# Board-Back.net
KiCad netlist of a schematic drawn in EAGLE
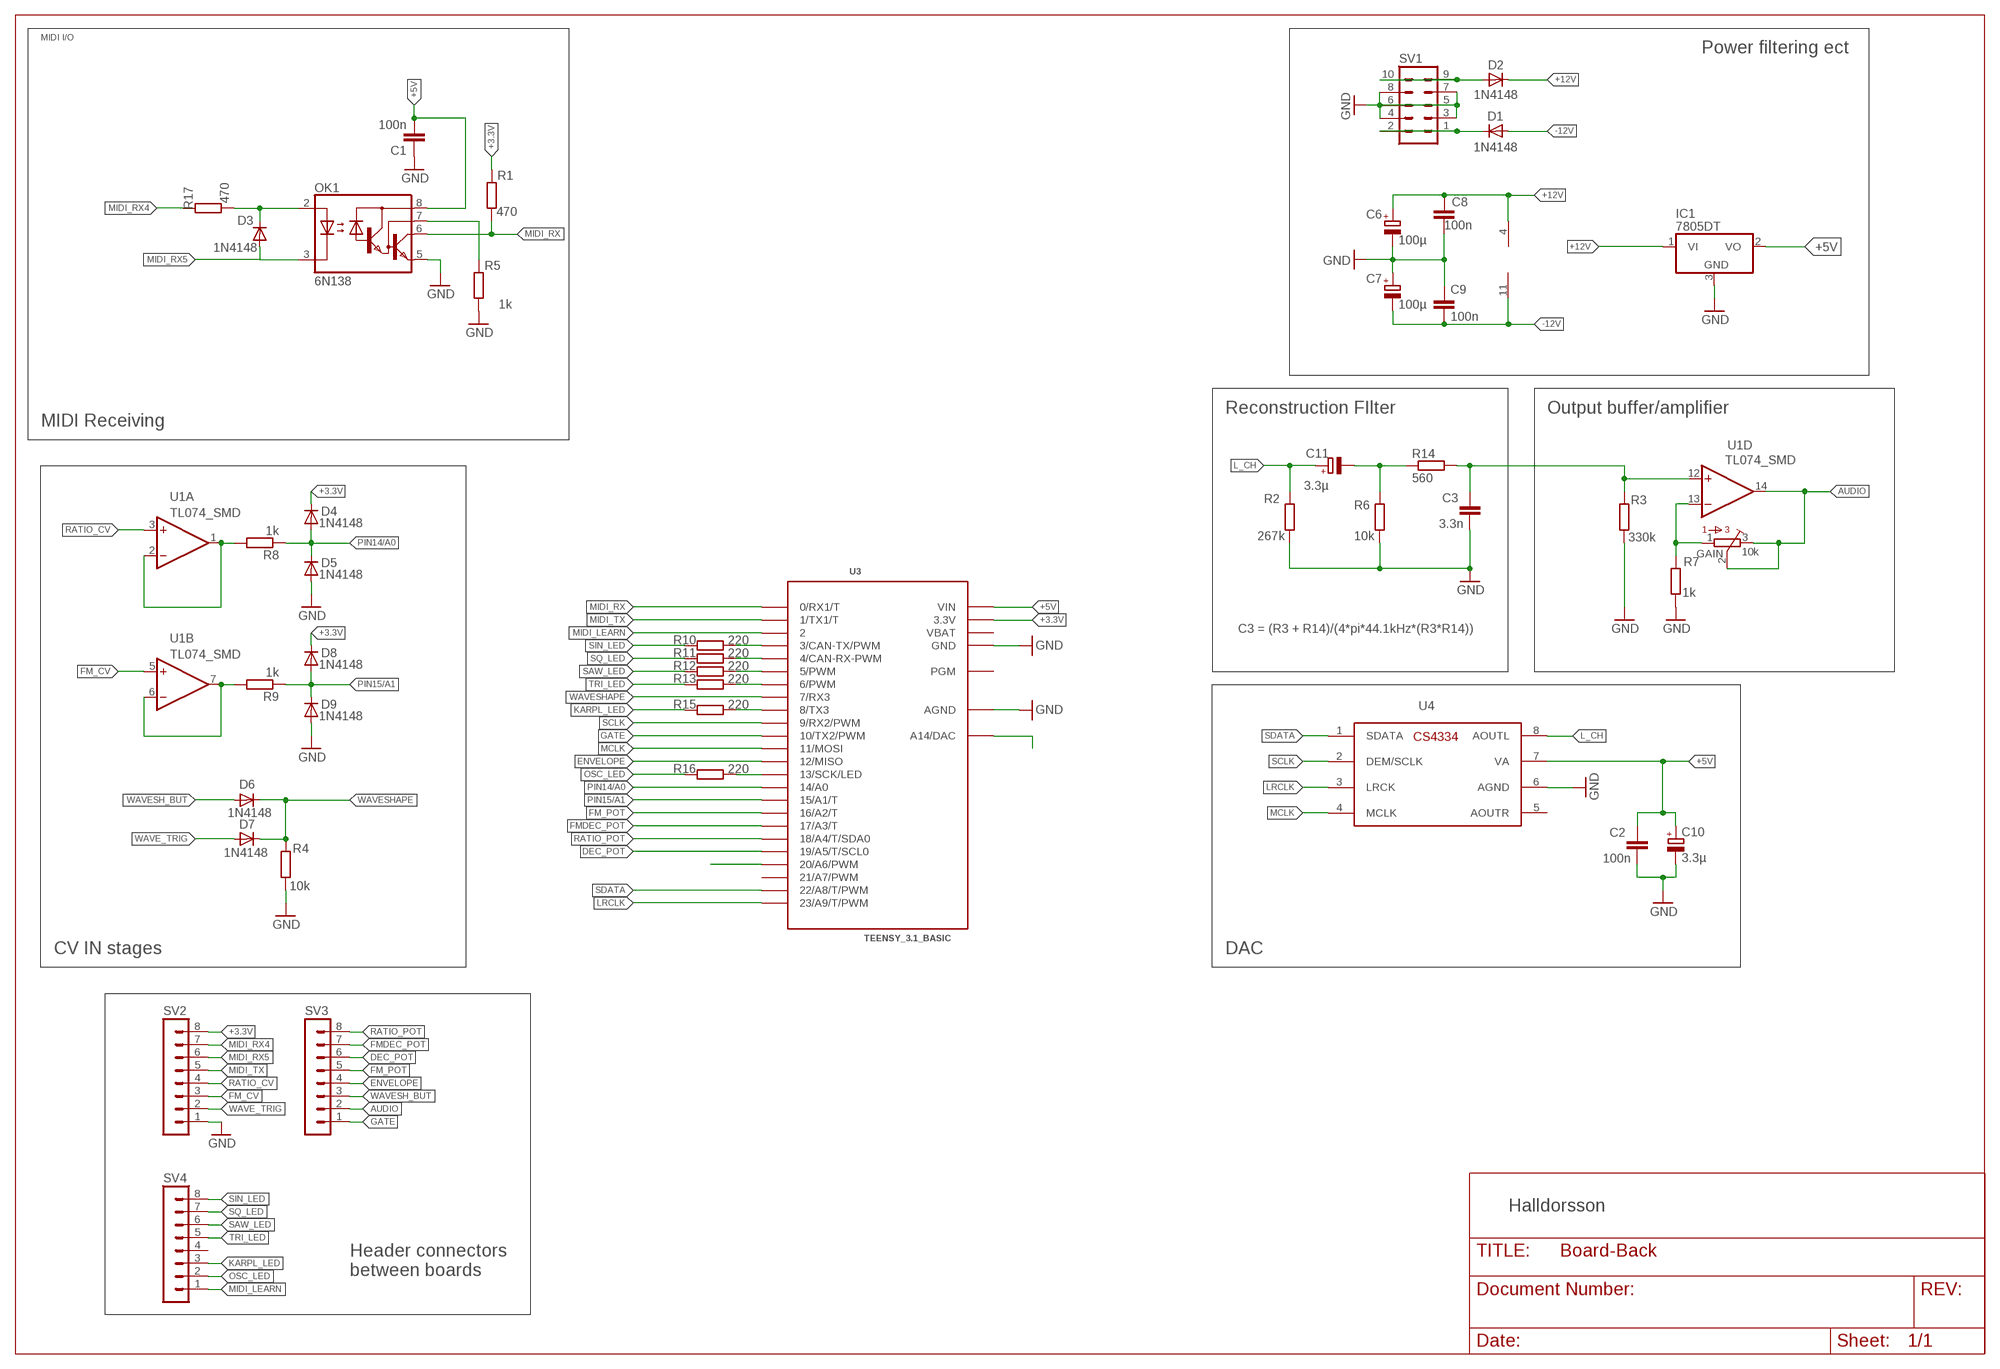
[diagram p0: schematic, sheet 1]

(export (version "E")
  (design (tool "Eeschema 10.0.6"))
  (components
    (comp (ref "C1")
      (value "100n")
      (footprint "eagle-import:C1206")
      (libsource (lib "eagle-import") (part "C-EUC1206"))
    )
    (comp (ref "C2")
      (value "100n")
      (footprint "eagle-import:C1206")
      (libsource (lib "eagle-import") (part "C-EUC1206"))
    )
    (comp (ref "C3")
      (value "3.3n")
      (footprint "eagle-import:C1206")
      (libsource (lib "eagle-import") (part "C-EUC1206"))
    )
    (comp (ref "C6")
      (value "100µ")
      (footprint "eagle-import:E5-6")
      (libsource (lib "eagle-import") (part "CPOL-EUE5-6"))
    )
    (comp (ref "C7")
      (value "100µ")
      (footprint "eagle-import:E5-6")
      (libsource (lib "eagle-import") (part "CPOL-EUE5-6"))
    )
    (comp (ref "C8")
      (value "100n")
      (footprint "eagle-import:C1206")
      (libsource (lib "eagle-import") (part "C-EUC1206"))
    )
    (comp (ref "C9")
      (value "100n")
      (footprint "eagle-import:C1206")
      (libsource (lib "eagle-import") (part "C-EUC1206"))
    )
    (comp (ref "C10")
      (value "3.3µ")
      (footprint "eagle-import:153CLV-0505")
      (libsource (lib "eagle-import") (part "CPOL-EU153CLV-0505"))
    )
    (comp (ref "C11")
      (value "3.3µ")
      (footprint "eagle-import:153CLV-0405")
      (libsource (lib "eagle-import") (part "CPOL-EU153CLV-0405"))
    )
    (comp (ref "D1")
      (value "1N4148")
      (footprint "eagle-import:DO35-7")
      (libsource (lib "eagle-import") (part "1N4148DO35-7"))
    )
    (comp (ref "D2")
      (value "1N4148")
      (footprint "eagle-import:DO35-7")
      (libsource (lib "eagle-import") (part "1N4148DO35-7"))
    )
    (comp (ref "D3")
      (value "1N4148")
      (footprint "eagle-import:DO35-7")
      (libsource (lib "eagle-import") (part "1N4148DO35-7"))
    )
    (comp (ref "D4")
      (value "1N4148")
      (footprint "eagle-import:DO35-7")
      (libsource (lib "eagle-import") (part "1N4148DO35-7"))
    )
    (comp (ref "D5")
      (value "1N4148")
      (footprint "eagle-import:DO35-7")
      (libsource (lib "eagle-import") (part "1N4148DO35-7"))
    )
    (comp (ref "D6")
      (value "1N4148")
      (footprint "eagle-import:DO35-7")
      (libsource (lib "eagle-import") (part "1N4148DO35-7"))
    )
    (comp (ref "D7")
      (value "1N4148")
      (footprint "eagle-import:DO35-7")
      (libsource (lib "eagle-import") (part "1N4148DO35-7"))
    )
    (comp (ref "D8")
      (value "1N4148")
      (footprint "eagle-import:DO35-7")
      (libsource (lib "eagle-import") (part "1N4148DO35-7"))
    )
    (comp (ref "D9")
      (value "1N4148")
      (footprint "eagle-import:DO35-7")
      (libsource (lib "eagle-import") (part "1N4148DO35-7"))
    )
    (comp (ref "GAIN")
      (value "10k")
      (footprint "eagle-import:BOURNS_3362P_TRIMMER")
      (libsource (lib "eagle-import") (part "BOURNS_3362P_TRIMMERP"))
    )
    (comp (ref "IC1")
      (value "7805DT")
      (footprint "eagle-import:TO252")
      (libsource (lib "eagle-import") (part "78DT05"))
    )
    (comp (ref "OK1")
      (value "6N138")
      (footprint "eagle-import:DIL08")
      (fields (field (name "MF") "VISHAY/TELEFUNKEN"))
      (libsource (lib "eagle-import") (part "6N138"))
    )
    (comp (ref "R1")
      (value "470")
      (footprint "eagle-import:M1206")
      (libsource (lib "eagle-import") (part "R-EU_M1206"))
    )
    (comp (ref "R2")
      (value "267k")
      (footprint "eagle-import:M1206")
      (libsource (lib "eagle-import") (part "R-EU_M1206"))
    )
    (comp (ref "R3")
      (value "330k")
      (footprint "eagle-import:M1206")
      (libsource (lib "eagle-import") (part "R-EU_M1206"))
    )
    (comp (ref "R4")
      (value "10k")
      (footprint "eagle-import:M1206")
      (libsource (lib "eagle-import") (part "R-EU_M1206"))
    )
    (comp (ref "R5")
      (value "1k")
      (footprint "eagle-import:M1206")
      (libsource (lib "eagle-import") (part "R-EU_M1206"))
    )
    (comp (ref "R6")
      (value "10k")
      (footprint "eagle-import:M1206")
      (libsource (lib "eagle-import") (part "R-EU_M1206"))
    )
    (comp (ref "R7")
      (value "1k")
      (footprint "eagle-import:M1206")
      (libsource (lib "eagle-import") (part "R-EU_M1206"))
    )
    (comp (ref "R8")
      (value "1k")
      (footprint "eagle-import:M1206")
      (libsource (lib "eagle-import") (part "R-EU_M1206"))
    )
    (comp (ref "R9")
      (value "1k")
      (footprint "eagle-import:M1206")
      (libsource (lib "eagle-import") (part "R-EU_M1206"))
    )
    (comp (ref "R10")
      (value "220")
      (footprint "eagle-import:M1206")
      (libsource (lib "eagle-import") (part "R-EU_M1206"))
    )
    (comp (ref "R11")
      (value "220")
      (footprint "eagle-import:M1206")
      (libsource (lib "eagle-import") (part "R-EU_M1206"))
    )
    (comp (ref "R12")
      (value "220")
      (footprint "eagle-import:M1206")
      (libsource (lib "eagle-import") (part "R-EU_M1206"))
    )
    (comp (ref "R13")
      (value "220")
      (footprint "eagle-import:M1206")
      (libsource (lib "eagle-import") (part "R-EU_M1206"))
    )
    (comp (ref "R14")
      (value "560")
      (footprint "eagle-import:M1206")
      (libsource (lib "eagle-import") (part "R-EU_M1206"))
    )
    (comp (ref "R15")
      (value "220")
      (footprint "eagle-import:M1206")
      (libsource (lib "eagle-import") (part "R-EU_M1206"))
    )
    (comp (ref "R16")
      (value "220")
      (footprint "eagle-import:M1206")
      (libsource (lib "eagle-import") (part "R-EU_M1206"))
    )
    (comp (ref "R17")
      (value "470")
      (footprint "eagle-import:M1206")
      (libsource (lib "eagle-import") (part "R-EU_M1206"))
    )
    (comp (ref "SV1")
      (value "10PIN_BACKSIDE")
      (footprint "eagle-import:10PIN_BACKSIDE")
      (libsource (lib "eagle-import") (part "10PIN_BACKSIDE"))
    )
    (comp (ref "SV2")
      (value "MA08-1")
      (footprint "eagle-import:MA08-1")
      (libsource (lib "eagle-import") (part "MA08-1"))
    )
    (comp (ref "SV3")
      (value "MA08-1")
      (footprint "eagle-import:MA08-1")
      (libsource (lib "eagle-import") (part "MA08-1"))
    )
    (comp (ref "SV4")
      (value "MA08-1")
      (footprint "eagle-import:MA08-1")
      (libsource (lib "eagle-import") (part "MA08-1"))
    )
    (comp (ref "U1")
      (value "TL074_SMD")
      (footprint "eagle-import:SO14")
      (libsource (lib "eagle-import") (part "TL074_SMD"))
    )
    (comp (ref "U3")
      (value "TEENSY_3.1_BASIC")
      (footprint "eagle-import:TEENSY_3.1_BASIC")
      (libsource (lib "eagle-import") (part "TEENSY_3.1_BASIC"))
    )
    (comp (ref "U4")
      (value "CS4334")
      (footprint "eagle-import:SOIC127P600X175-8N")
      (libsource (lib "eagle-import") (part "CS4334"))
    )
  )
  (nets
    (net (code "1") (name "+3.3V") (class "Default")
      (node (ref "D4") (pin "C") (pinfunction "C_C") (pintype "passive"))
      (node (ref "D8") (pin "C") (pinfunction "C_C") (pintype "passive"))
      (node (ref "R1") (pin "2") (pinfunction "2_2") (pintype "passive"))
      (node (ref "SV2") (pin "8") (pinfunction "8_8") (pintype "passive"))
      (node (ref "U3") (pin "3.3V") (pinfunction "3.3V_3.3V") (pintype "power_in"))
      (node (ref "U3") (pin "3.3V1") (pinfunction "3.3V_3.3V1") (pintype "power_in"))
    )
    (net (code "2") (name "+5V") (class "Default")
      (node (ref "C1") (pin "2") (pinfunction "2_2") (pintype "passive"))
      (node (ref "C10") (pin "+") (pinfunction "+_+") (pintype "passive"))
      (node (ref "C2") (pin "1") (pinfunction "1_1") (pintype "passive"))
      (node (ref "IC1") (pin "2") (pinfunction "VO_2") (pintype "passive"))
      (node (ref "OK1") (pin "8") (pinfunction "VCC_8") (pintype "passive"))
      (node (ref "U3") (pin "VIN") (pinfunction "VIN_VIN") (pintype "power_in"))
      (node (ref "U4") (pin "7") (pinfunction "VA_7") (pintype "bidirectional"))
    )
    (net (code "3") (name "+12V") (class "Default")
      (node (ref "C6") (pin "+") (pinfunction "+_+") (pintype "passive"))
      (node (ref "C8") (pin "1") (pinfunction "1_1") (pintype "passive"))
      (node (ref "D2") (pin "C") (pinfunction "C_C") (pintype "passive"))
      (node (ref "IC1") (pin "1") (pinfunction "VI_1") (pintype "input"))
      (node (ref "U1") (pin "4") (pinfunction "V+_4") (pintype "power_in"))
    )
    (net (code "4") (name "-12V") (class "Default")
      (node (ref "C7") (pin "-") (pinfunction "-_-") (pintype "passive"))
      (node (ref "C9") (pin "2") (pinfunction "2_2") (pintype "passive"))
      (node (ref "D1") (pin "A") (pinfunction "A_A") (pintype "passive"))
      (node (ref "U1") (pin "11") (pinfunction "V-_11") (pintype "power_in"))
    )
    (net (code "5") (name "/VBAT") (class "Default")
      (node (ref "U3") (pin "VBAT") (pinfunction "VBAT_VBAT") (pintype "power_in"))
    )
    (net (code "6") (name "AUDIO") (class "Default")
      (node (ref "GAIN") (pin "2") (pinfunction "2_2") (pintype "passive"))
      (node (ref "GAIN") (pin "3") (pinfunction "3_3") (pintype "passive"))
      (node (ref "SV3") (pin "2") (pinfunction "2_2") (pintype "passive"))
      (node (ref "U1") (pin "14") (pinfunction "OUT_14") (pintype "output"))
    )
    (net (code "7") (name "DEC_POT") (class "Default")
      (node (ref "SV3") (pin "6") (pinfunction "6_6") (pintype "passive"))
      (node (ref "U3") (pin "19/A5") (pinfunction "19/A5/T/SCL0_19/A5") (pintype "bidirectional"))
    )
    (net (code "8") (name "ENVELOPE") (class "Default")
      (node (ref "SV3") (pin "4") (pinfunction "4_4") (pintype "passive"))
      (node (ref "U3") (pin "12") (pinfunction "12/MISO_12") (pintype "bidirectional"))
    )
    (net (code "9") (name "FMDEC_POT") (class "Default")
      (node (ref "SV3") (pin "7") (pinfunction "7_7") (pintype "passive"))
      (node (ref "U3") (pin "17/A3") (pinfunction "17/A3/T_17/A3") (pintype "bidirectional"))
    )
    (net (code "10") (name "FM_CV") (class "Default")
      (node (ref "SV2") (pin "3") (pinfunction "3_3") (pintype "passive"))
      (node (ref "U1") (pin "5") (pinfunction "+IN_5") (pintype "input"))
    )
    (net (code "11") (name "FM_POT") (class "Default")
      (node (ref "SV3") (pin "5") (pinfunction "5_5") (pintype "passive"))
      (node (ref "U3") (pin "16/A2") (pinfunction "16/A2/T_16/A2") (pintype "bidirectional"))
    )
    (net (code "12") (name "GATE") (class "Default")
      (node (ref "SV3") (pin "1") (pinfunction "1_1") (pintype "passive"))
      (node (ref "U3") (pin "10") (pinfunction "10/TX2/PWM_10") (pintype "bidirectional"))
    )
    (net (code "13") (name "GND") (class "Default")
      (node (ref "C1") (pin "1") (pinfunction "1_1") (pintype "passive"))
      (node (ref "C10") (pin "-") (pinfunction "-_-") (pintype "passive"))
      (node (ref "C2") (pin "2") (pinfunction "2_2") (pintype "passive"))
      (node (ref "C3") (pin "2") (pinfunction "2_2") (pintype "passive"))
      (node (ref "C6") (pin "-") (pinfunction "-_-") (pintype "passive"))
      (node (ref "C7") (pin "+") (pinfunction "+_+") (pintype "passive"))
      (node (ref "C8") (pin "2") (pinfunction "2_2") (pintype "passive"))
      (node (ref "C9") (pin "1") (pinfunction "1_1") (pintype "passive"))
      (node (ref "D5") (pin "A") (pinfunction "A_A") (pintype "passive"))
      (node (ref "D9") (pin "A") (pinfunction "A_A") (pintype "passive"))
      (node (ref "IC1") (pin "3") (pinfunction "GND_3") (pintype "passive"))
      (node (ref "OK1") (pin "5") (pinfunction "GND_5") (pintype "passive"))
      (node (ref "R2") (pin "2") (pinfunction "2_2") (pintype "passive"))
      (node (ref "R3") (pin "2") (pinfunction "2_2") (pintype "passive"))
      (node (ref "R4") (pin "1") (pinfunction "1_1") (pintype "passive"))
      (node (ref "R5") (pin "1") (pinfunction "1_1") (pintype "passive"))
      (node (ref "R6") (pin "2") (pinfunction "2_2") (pintype "passive"))
      (node (ref "R7") (pin "2") (pinfunction "2_2") (pintype "passive"))
      (node (ref "SV1") (pin "3") (pinfunction "3_3") (pintype "passive"))
      (node (ref "SV1") (pin "4") (pinfunction "4_4") (pintype "passive"))
      (node (ref "SV1") (pin "5") (pinfunction "5_5") (pintype "passive"))
      (node (ref "SV1") (pin "6") (pinfunction "6_6") (pintype "passive"))
      (node (ref "SV1") (pin "7") (pinfunction "7_7") (pintype "passive"))
      (node (ref "SV1") (pin "8") (pinfunction "8_8") (pintype "passive"))
      (node (ref "SV2") (pin "1") (pinfunction "1_1") (pintype "passive"))
      (node (ref "U3") (pin "AGND") (pinfunction "AGND_AGND") (pintype "power_in"))
      (node (ref "U3") (pin "GND") (pinfunction "GND_GND") (pintype "power_in"))
      (node (ref "U3") (pin "GND1") (pinfunction "GND_GND1") (pintype "power_in"))
      (node (ref "U4") (pin "6") (pinfunction "AGND_6") (pintype "bidirectional"))
    )
    (net (code "14") (name "KARPL_LED") (class "Default")
      (node (ref "R15") (pin "2") (pinfunction "2_2") (pintype "passive"))
      (node (ref "SV4") (pin "3") (pinfunction "3_3") (pintype "passive"))
    )
    (net (code "15") (name "LRCLK") (class "Default")
      (node (ref "U3") (pin "23/A9") (pinfunction "23/A9/T/PWM_23/A9") (pintype "bidirectional"))
      (node (ref "U4") (pin "3") (pinfunction "LRCK_3") (pintype "bidirectional"))
    )
    (net (code "16") (name "L_CH") (class "Default")
      (node (ref "C11") (pin "+") (pinfunction "+_+") (pintype "passive"))
      (node (ref "R2") (pin "1") (pinfunction "1_1") (pintype "passive"))
      (node (ref "U4") (pin "8") (pinfunction "AOUTL_8") (pintype "bidirectional"))
    )
    (net (code "17") (name "MCLK") (class "Default")
      (node (ref "U3") (pin "11") (pinfunction "11/MOSI_11") (pintype "bidirectional"))
      (node (ref "U4") (pin "4") (pinfunction "MCLK_4") (pintype "bidirectional"))
    )
    (net (code "18") (name "MIDI_LEARN") (class "Default")
      (node (ref "SV4") (pin "1") (pinfunction "1_1") (pintype "passive"))
      (node (ref "U3") (pin "2") (pinfunction "2_2") (pintype "bidirectional"))
    )
    (net (code "19") (name "MIDI_RX") (class "Default")
      (node (ref "OK1") (pin "6") (pinfunction "VO_6") (pintype "passive"))
      (node (ref "R1") (pin "1") (pinfunction "1_1") (pintype "passive"))
      (node (ref "U3") (pin "0") (pinfunction "0/RX1/T_0") (pintype "bidirectional"))
    )
    (net (code "20") (name "MIDI_RX4") (class "Default")
      (node (ref "R17") (pin "2") (pinfunction "2_2") (pintype "passive"))
      (node (ref "SV2") (pin "7") (pinfunction "7_7") (pintype "passive"))
    )
    (net (code "21") (name "MIDI_RX5") (class "Default")
      (node (ref "D3") (pin "A") (pinfunction "A_A") (pintype "passive"))
      (node (ref "OK1") (pin "3") (pinfunction "C_3") (pintype "passive"))
      (node (ref "SV2") (pin "6") (pinfunction "6_6") (pintype "passive"))
    )
    (net (code "22") (name "MIDI_TX") (class "Default")
      (node (ref "SV2") (pin "5") (pinfunction "5_5") (pintype "passive"))
      (node (ref "U3") (pin "1") (pinfunction "1/TX1/T_1") (pintype "bidirectional"))
    )
    (net (code "23") (name "Net-(C11-Pad-)") (class "Default")
      (node (ref "C11") (pin "-") (pinfunction "-_-") (pintype "passive"))
      (node (ref "R14") (pin "1") (pinfunction "1_1") (pintype "passive"))
      (node (ref "R6") (pin "1") (pinfunction "1_1") (pintype "passive"))
    )
    (net (code "24") (name "Net-(D1-PadC)") (class "Default")
      (node (ref "D1") (pin "C") (pinfunction "C_C") (pintype "passive"))
      (node (ref "SV1") (pin "1") (pinfunction "1_1") (pintype "passive"))
      (node (ref "SV1") (pin "2") (pinfunction "2_2") (pintype "passive"))
    )
    (net (code "25") (name "Net-(D2-PadA)") (class "Default")
      (node (ref "D2") (pin "A") (pinfunction "A_A") (pintype "passive"))
      (node (ref "SV1") (pin "10") (pinfunction "10_10") (pintype "passive"))
      (node (ref "SV1") (pin "9") (pinfunction "9_9") (pintype "passive"))
    )
    (net (code "26") (name "Net-(OK1-A)") (class "Default")
      (node (ref "D3") (pin "C") (pinfunction "C_C") (pintype "passive"))
      (node (ref "OK1") (pin "2") (pinfunction "A_2") (pintype "passive"))
      (node (ref "R17") (pin "1") (pinfunction "1_1") (pintype "passive"))
    )
    (net (code "27") (name "Net-(OK1-VB)") (class "Default")
      (node (ref "OK1") (pin "7") (pinfunction "VB_7") (pintype "passive"))
      (node (ref "R5") (pin "2") (pinfunction "2_2") (pintype "passive"))
    )
    (net (code "28") (name "Net-(U1A--IN)") (class "Default")
      (node (ref "R8") (pin "2") (pinfunction "2_2") (pintype "passive"))
      (node (ref "U1") (pin "1") (pinfunction "OUT_1") (pintype "output"))
      (node (ref "U1") (pin "2") (pinfunction "-IN_2") (pintype "input"))
    )
    (net (code "29") (name "Net-(U1B--IN)") (class "Default")
      (node (ref "R9") (pin "2") (pinfunction "2_2") (pintype "passive"))
      (node (ref "U1") (pin "6") (pinfunction "-IN_6") (pintype "input"))
      (node (ref "U1") (pin "7") (pinfunction "OUT_7") (pintype "output"))
    )
    (net (code "30") (name "Net-(U1D-+IN)") (class "Default")
      (node (ref "C3") (pin "1") (pinfunction "1_1") (pintype "passive"))
      (node (ref "R14") (pin "2") (pinfunction "2_2") (pintype "passive"))
      (node (ref "R3") (pin "1") (pinfunction "1_1") (pintype "passive"))
      (node (ref "U1") (pin "12") (pinfunction "+IN_12") (pintype "input"))
    )
    (net (code "31") (name "Net-(U1D--IN)") (class "Default")
      (node (ref "GAIN") (pin "1") (pinfunction "1_1") (pintype "passive"))
      (node (ref "R7") (pin "1") (pinfunction "1_1") (pintype "passive"))
      (node (ref "U1") (pin "13") (pinfunction "-IN_13") (pintype "input"))
    )
    (net (code "32") (name "Net-(U3-3{slash}CAN-TX{slash}PWM)") (class "Default")
      (node (ref "R10") (pin "1") (pinfunction "1_1") (pintype "passive"))
      (node (ref "U3") (pin "3") (pinfunction "3/CAN-TX/PWM_3") (pintype "bidirectional"))
    )
    (net (code "33") (name "Net-(U3-4{slash}CAN-RX-PWM)") (class "Default")
      (node (ref "R11") (pin "1") (pinfunction "1_1") (pintype "passive"))
      (node (ref "U3") (pin "4") (pinfunction "4/CAN-RX-PWM_4") (pintype "bidirectional"))
    )
    (net (code "34") (name "Net-(U3-5{slash}PWM)") (class "Default")
      (node (ref "R12") (pin "1") (pinfunction "1_1") (pintype "passive"))
      (node (ref "U3") (pin "5") (pinfunction "5/PWM_5") (pintype "bidirectional"))
    )
    (net (code "35") (name "Net-(U3-6{slash}PWM)") (class "Default")
      (node (ref "R13") (pin "1") (pinfunction "1_1") (pintype "passive"))
      (node (ref "U3") (pin "6") (pinfunction "6/PWM_6") (pintype "bidirectional"))
    )
    (net (code "36") (name "Net-(U3-8{slash}TX3)") (class "Default")
      (node (ref "R15") (pin "1") (pinfunction "1_1") (pintype "passive"))
      (node (ref "U3") (pin "8") (pinfunction "8/TX3_8") (pintype "bidirectional"))
    )
    (net (code "37") (name "Net-(U3-13{slash}SCK{slash}LED)") (class "Default")
      (node (ref "R16") (pin "1") (pinfunction "1_1") (pintype "passive"))
      (node (ref "U3") (pin "13") (pinfunction "13/SCK/LED_13") (pintype "bidirectional"))
    )
    (net (code "38") (name "OSC_LED") (class "Default")
      (node (ref "R16") (pin "2") (pinfunction "2_2") (pintype "passive"))
      (node (ref "SV4") (pin "2") (pinfunction "2_2") (pintype "passive"))
    )
    (net (code "39") (name "PIN14{slash}A0") (class "Default")
      (node (ref "D4") (pin "A") (pinfunction "A_A") (pintype "passive"))
      (node (ref "D5") (pin "C") (pinfunction "C_C") (pintype "passive"))
      (node (ref "R8") (pin "1") (pinfunction "1_1") (pintype "passive"))
      (node (ref "U3") (pin "14/A0") (pinfunction "14/A0_14/A0") (pintype "bidirectional"))
    )
    (net (code "40") (name "PIN15{slash}A1") (class "Default")
      (node (ref "D8") (pin "A") (pinfunction "A_A") (pintype "passive"))
      (node (ref "D9") (pin "C") (pinfunction "C_C") (pintype "passive"))
      (node (ref "R9") (pin "1") (pinfunction "1_1") (pintype "passive"))
      (node (ref "U3") (pin "15/A1") (pinfunction "15/A1/T_15/A1") (pintype "bidirectional"))
    )
    (net (code "41") (name "RATIO_CV") (class "Default")
      (node (ref "SV2") (pin "4") (pinfunction "4_4") (pintype "passive"))
      (node (ref "U1") (pin "3") (pinfunction "+IN_3") (pintype "input"))
    )
    (net (code "42") (name "RATIO_POT") (class "Default")
      (node (ref "SV3") (pin "8") (pinfunction "8_8") (pintype "passive"))
      (node (ref "U3") (pin "18/A4") (pinfunction "18/A4/T/SDA0_18/A4") (pintype "bidirectional"))
    )
    (net (code "43") (name "SAW_LED") (class "Default")
      (node (ref "R12") (pin "2") (pinfunction "2_2") (pintype "passive"))
      (node (ref "SV4") (pin "6") (pinfunction "6_6") (pintype "passive"))
    )
    (net (code "44") (name "SCLK") (class "Default")
      (node (ref "U3") (pin "9") (pinfunction "9/RX2/PWM_9") (pintype "bidirectional"))
      (node (ref "U4") (pin "2") (pinfunction "DEM/SCLK_2") (pintype "bidirectional"))
    )
    (net (code "45") (name "SDATA") (class "Default")
      (node (ref "U3") (pin "22/A8") (pinfunction "22/A8/T/PWM_22/A8") (pintype "bidirectional"))
      (node (ref "U4") (pin "1") (pinfunction "SDATA_1") (pintype "bidirectional"))
    )
    (net (code "46") (name "SIN_LED") (class "Default")
      (node (ref "R10") (pin "2") (pinfunction "2_2") (pintype "passive"))
      (node (ref "SV4") (pin "8") (pinfunction "8_8") (pintype "passive"))
    )
    (net (code "47") (name "SQ_LED") (class "Default")
      (node (ref "R11") (pin "2") (pinfunction "2_2") (pintype "passive"))
      (node (ref "SV4") (pin "7") (pinfunction "7_7") (pintype "passive"))
    )
    (net (code "48") (name "TRI_LED") (class "Default")
      (node (ref "R13") (pin "2") (pinfunction "2_2") (pintype "passive"))
      (node (ref "SV4") (pin "5") (pinfunction "5_5") (pintype "passive"))
    )
    (net (code "49") (name "WAVESHAPE") (class "Default")
      (node (ref "D6") (pin "C") (pinfunction "C_C") (pintype "passive"))
      (node (ref "D7") (pin "C") (pinfunction "C_C") (pintype "passive"))
      (node (ref "R4") (pin "2") (pinfunction "2_2") (pintype "passive"))
      (node (ref "U3") (pin "7") (pinfunction "7/RX3_7") (pintype "bidirectional"))
    )
    (net (code "50") (name "WAVESH_BUT") (class "Default")
      (node (ref "D6") (pin "A") (pinfunction "A_A") (pintype "passive"))
      (node (ref "SV3") (pin "3") (pinfunction "3_3") (pintype "passive"))
    )
    (net (code "51") (name "WAVE_TRIG") (class "Default")
      (node (ref "D7") (pin "A") (pinfunction "A_A") (pintype "passive"))
      (node (ref "SV2") (pin "2") (pinfunction "2_2") (pintype "passive"))
    )
    (net (code "52") (name "unconnected-(SV4-Pad4)") (class "Default")
      (node (ref "SV4") (pin "4") (pinfunction "4_4") (pintype "passive"))
    )
    (net (code "53") (name "unconnected-(U3-20{slash}A6{slash}PWM-Pad20{slash}A6)") (class "Default")
      (node (ref "U3") (pin "20/A6") (pinfunction "20/A6/PWM_20/A6") (pintype "bidirectional"))
    )
    (net (code "54") (name "unconnected-(U3-21{slash}A7{slash}PWM-Pad21{slash}A7)") (class "Default")
      (node (ref "U3") (pin "21/A7") (pinfunction "21/A7/PWM_21/A7") (pintype "bidirectional"))
    )
    (net (code "55") (name "unconnected-(U3-A14{slash}DAC-PadA14)") (class "Default")
      (node (ref "U3") (pin "A14") (pinfunction "A14/DAC_A14") (pintype "bidirectional"))
    )
    (net (code "56") (name "unconnected-(U3-PadPGM)") (class "Default")
      (node (ref "U3") (pin "PGM") (pinfunction "PGM_PGM") (pintype "bidirectional"))
    )
    (net (code "57") (name "unconnected-(U4-AOUTR-Pad5)") (class "Default")
      (node (ref "U4") (pin "5") (pinfunction "AOUTR_5") (pintype "bidirectional"))
    )
  )
)
